# main.net
KiCad netlist of a schematic drawn in EAGLE
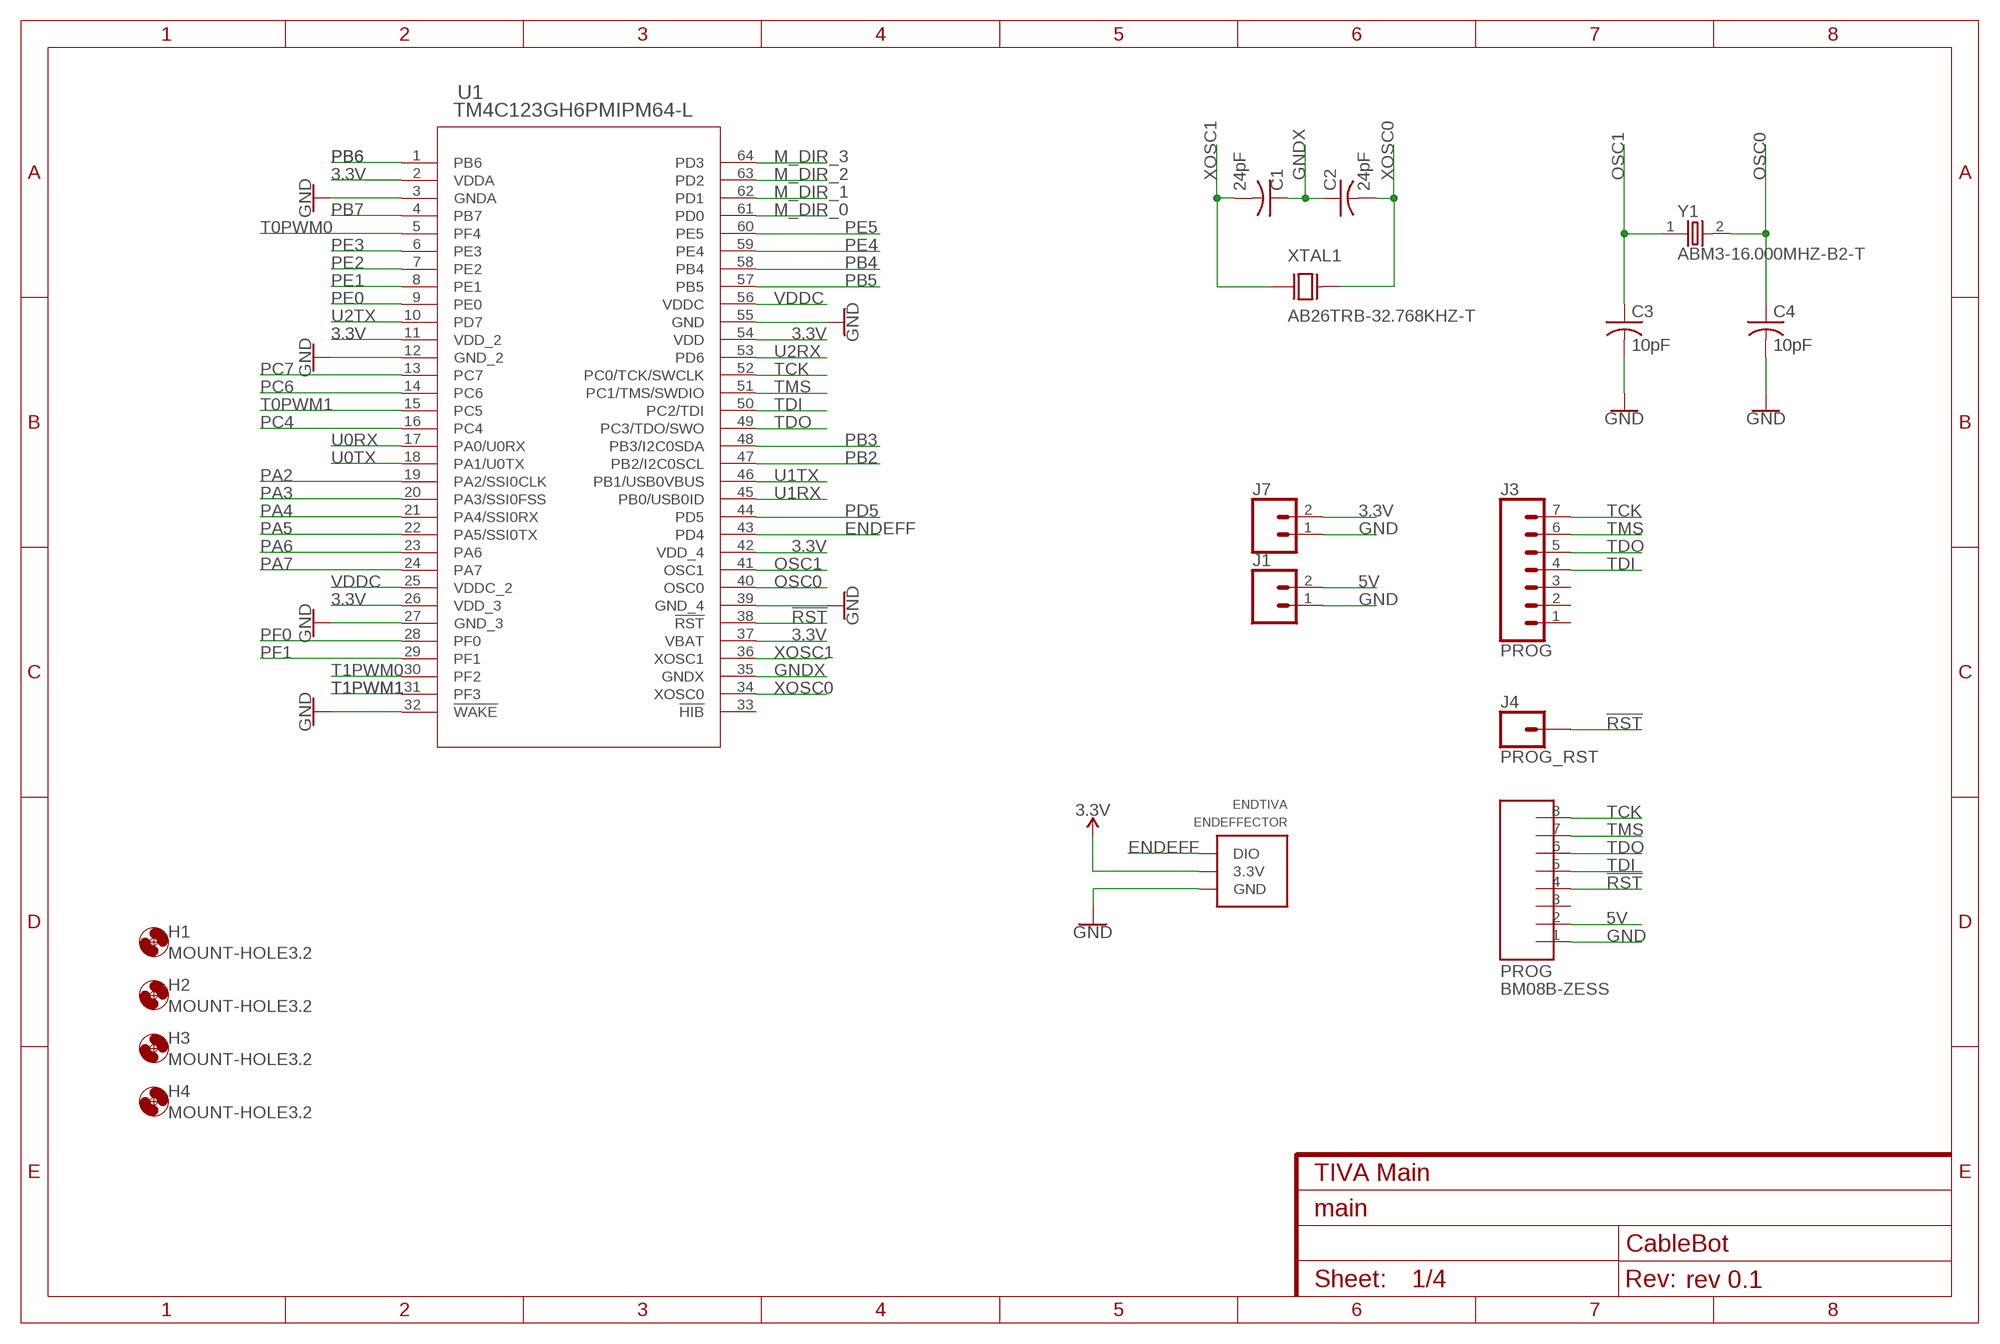
[diagram p0: schematic, sheet 1]
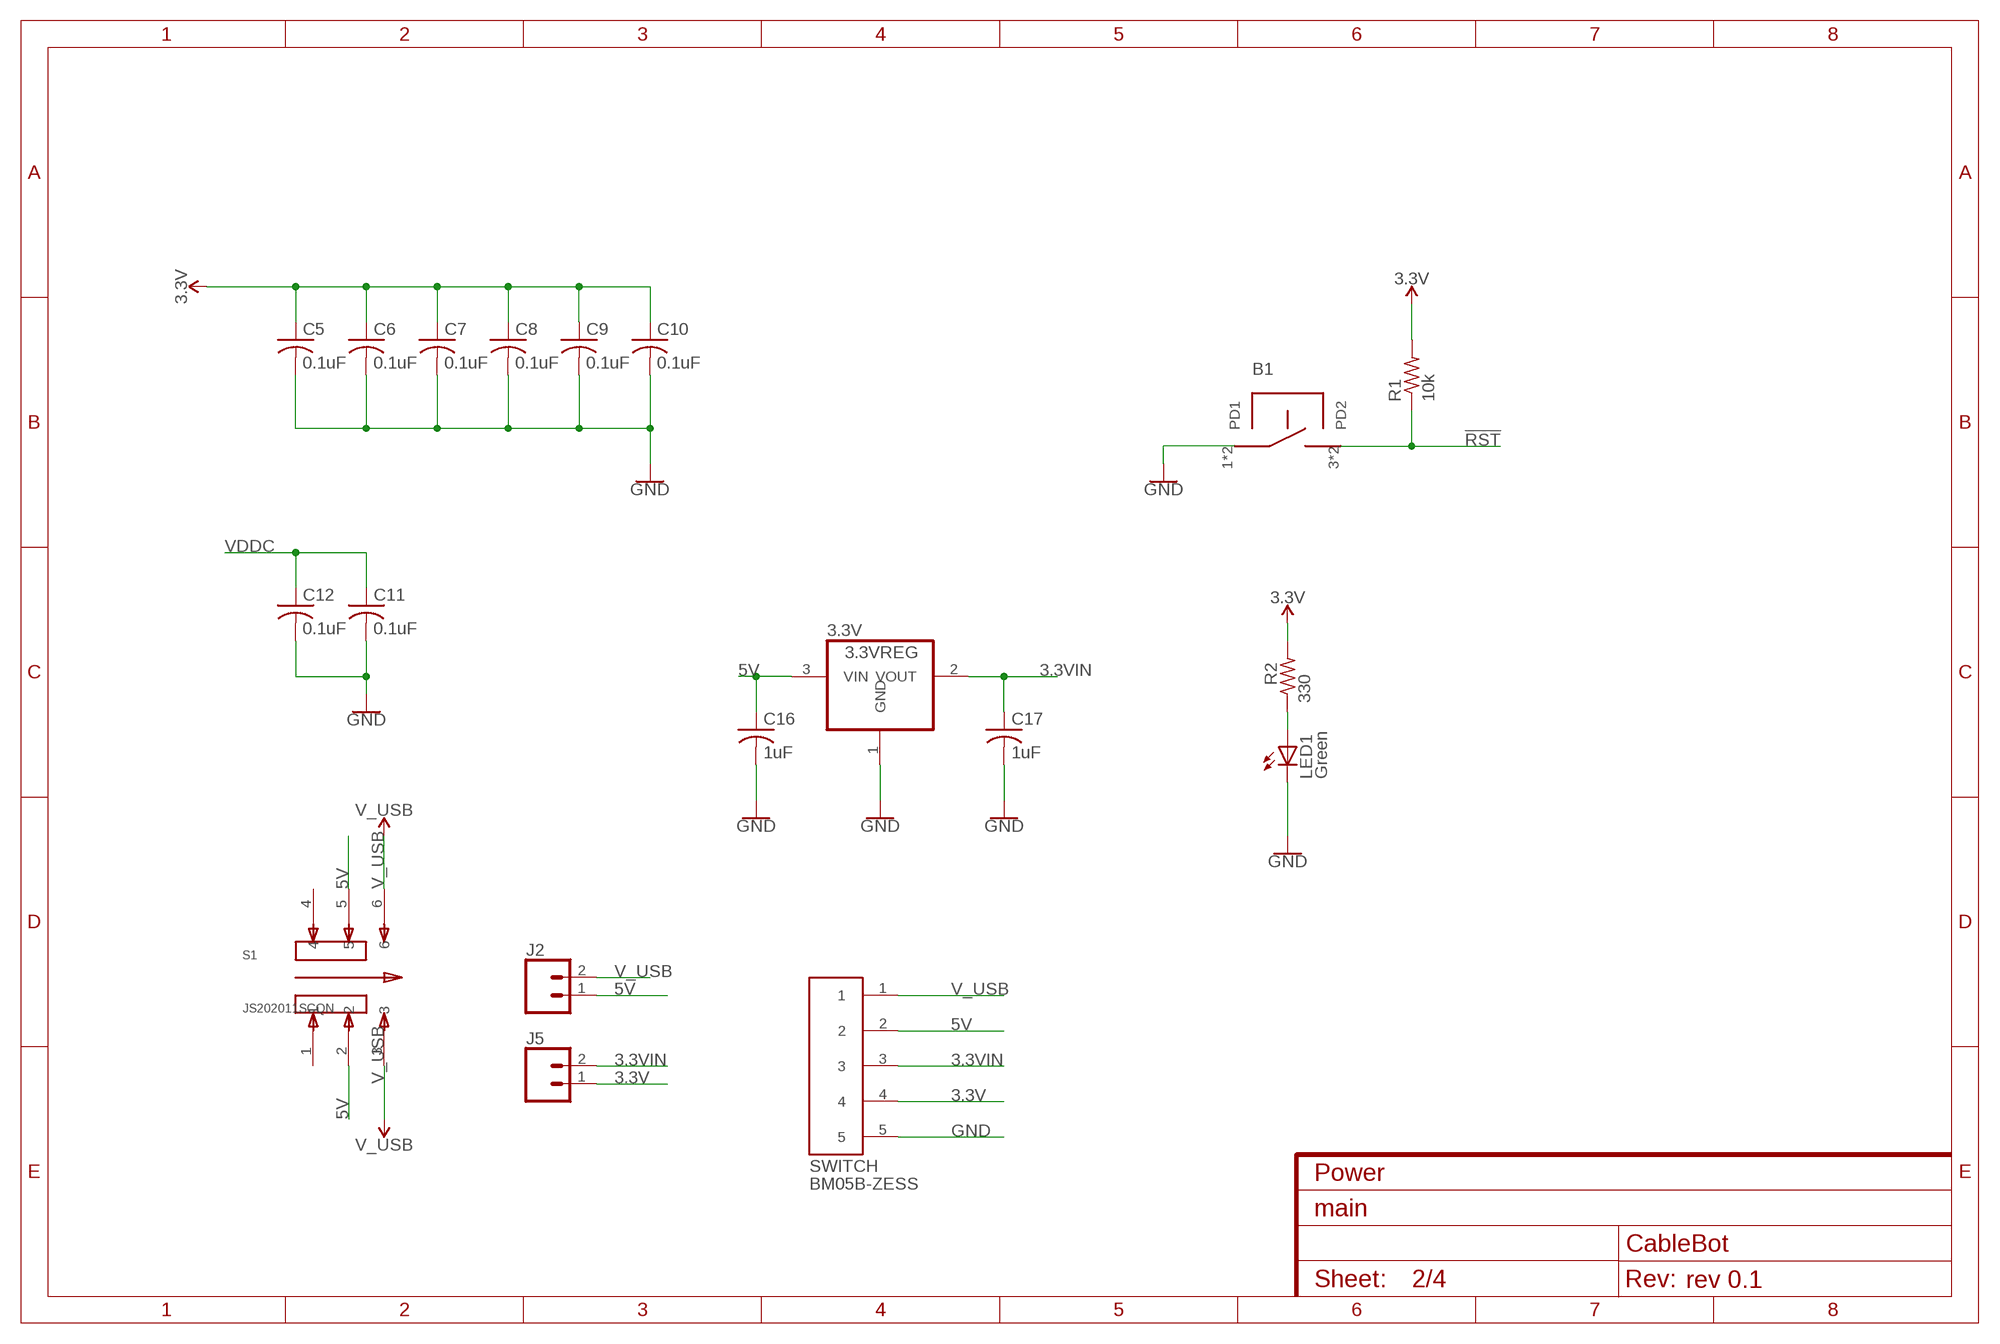
[diagram p1: schematic, sheet 2]
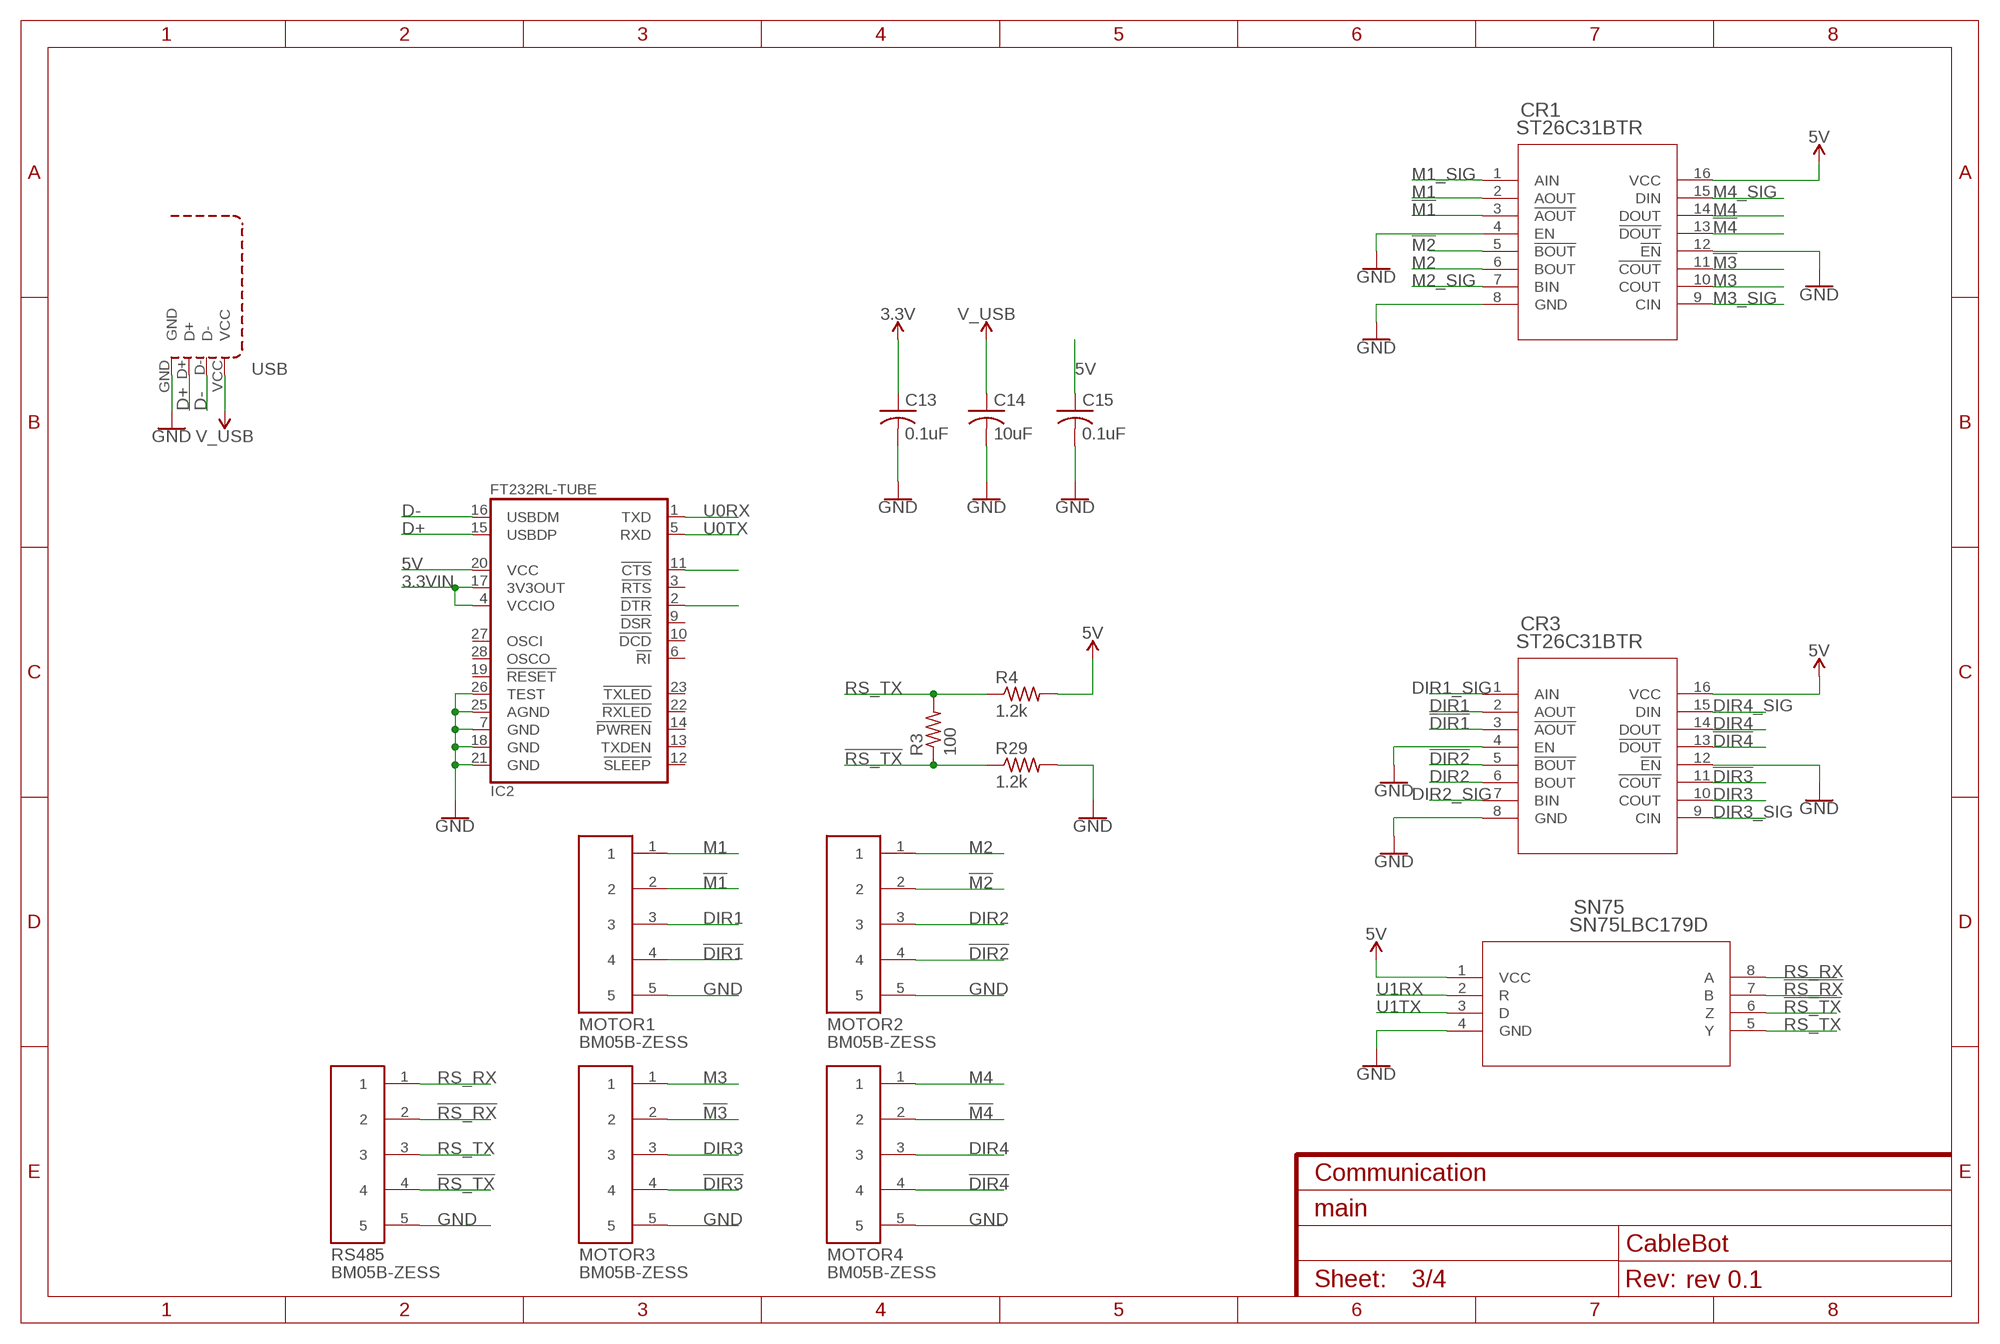
[diagram p2: schematic, sheet 3]
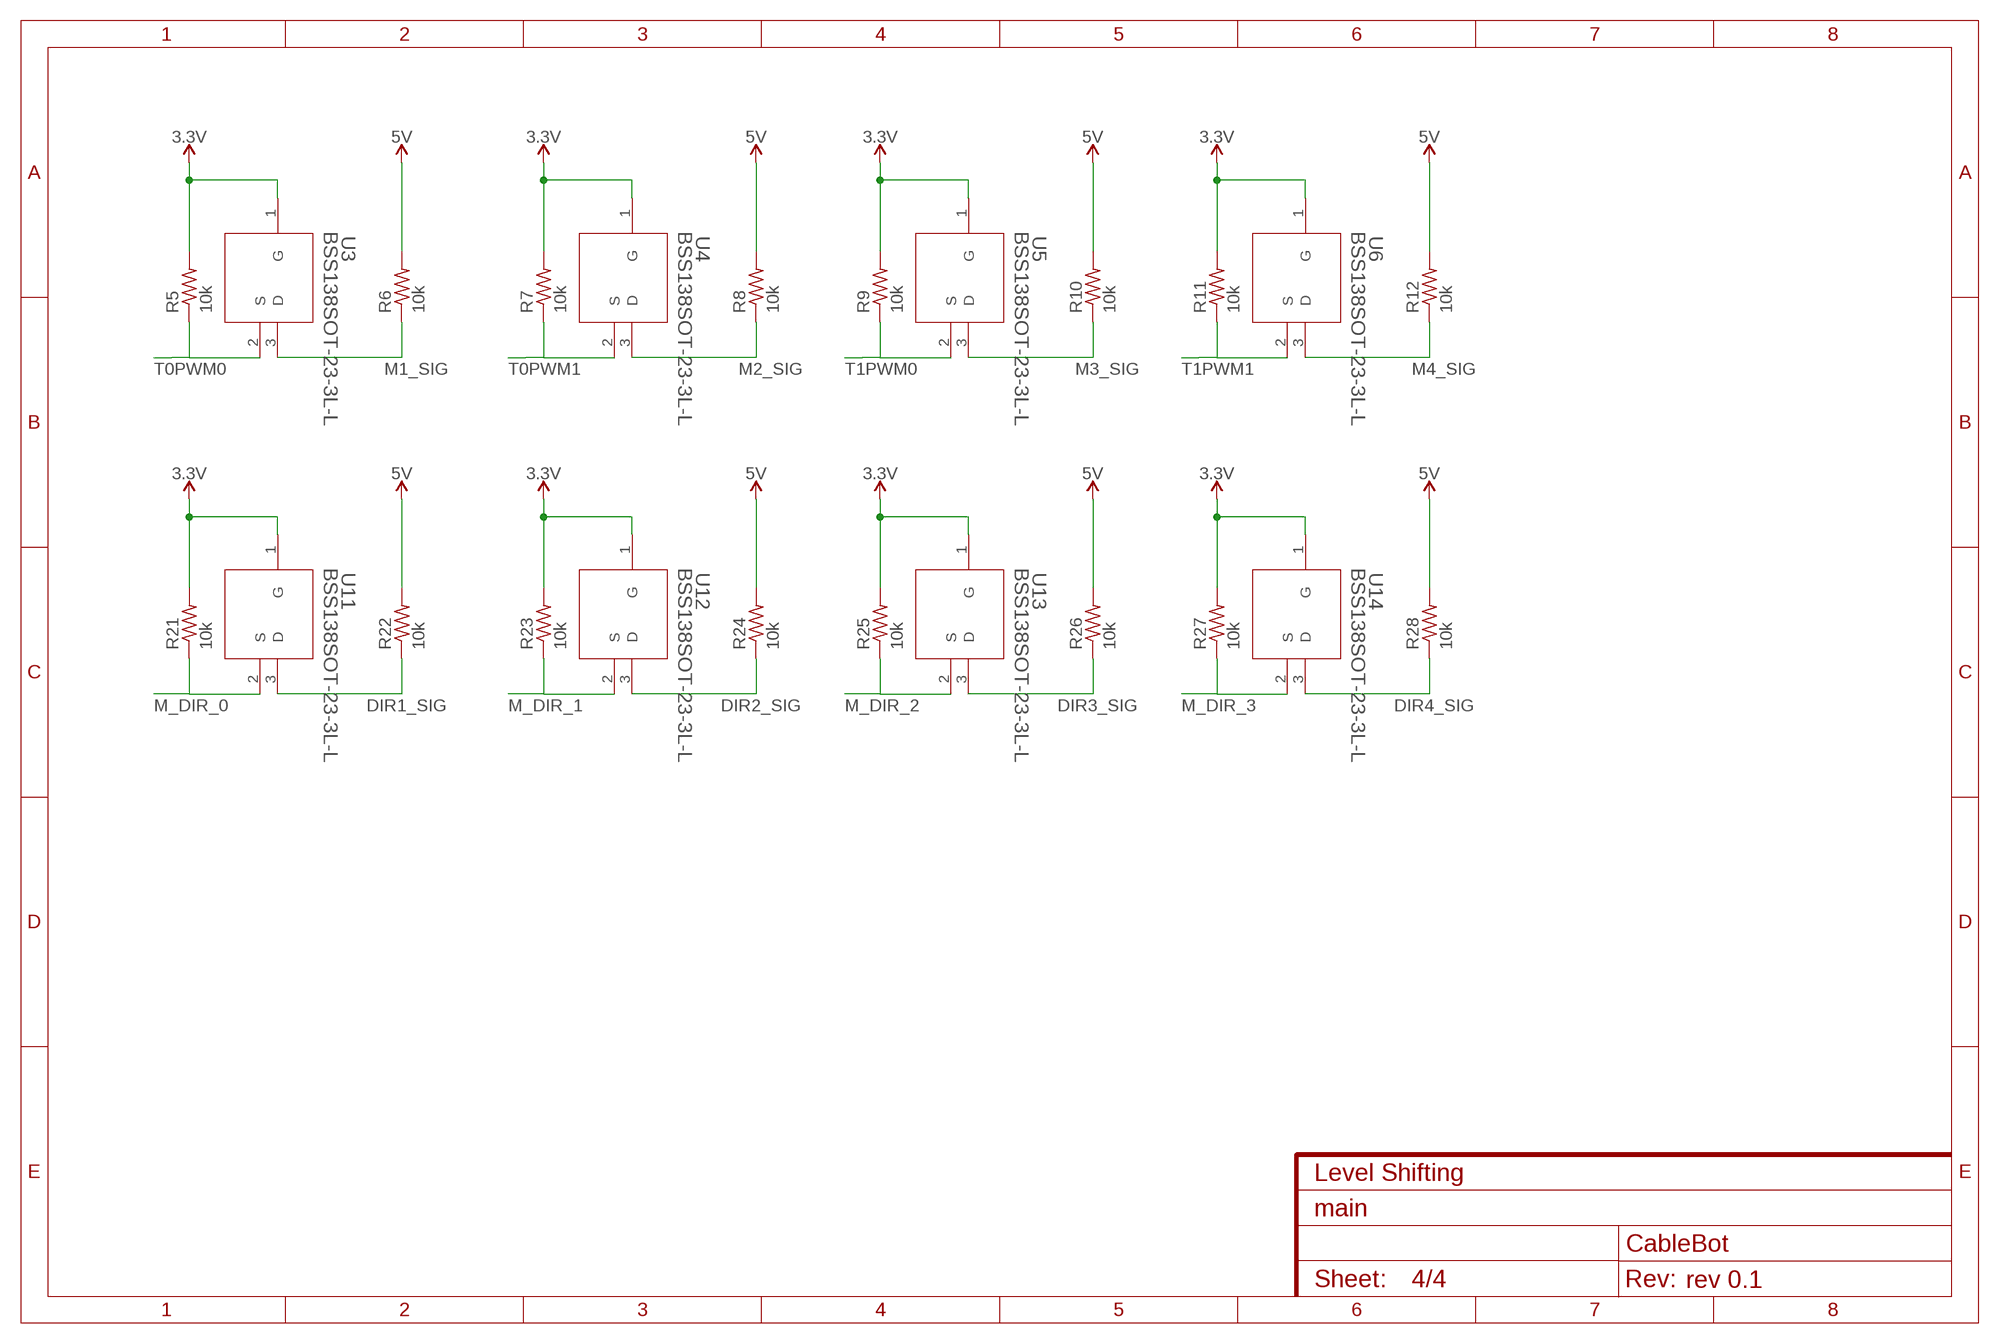
[diagram p3: schematic, sheet 4]

(export (version "E")
  (design (tool "Eeschema 10.0.6"))
  (components
    (comp (ref "C1")
      (value "24pF")
      (footprint "eagle-import:C0805")
      (libsource (lib "eagle-import") (part "C-USC0805"))
    )
    (comp (ref "C2")
      (value "24pF")
      (footprint "eagle-import:C0805")
      (libsource (lib "eagle-import") (part "C-USC0805"))
    )
    (comp (ref "C3")
      (value "10pF")
      (footprint "eagle-import:C0805")
      (libsource (lib "eagle-import") (part "C-USC0805"))
    )
    (comp (ref "C4")
      (value "10pF")
      (footprint "eagle-import:C0805")
      (libsource (lib "eagle-import") (part "C-USC0805"))
    )
    (comp (ref "ENDEFFECTOR")
      (value "ENDTIVA")
      (footprint "eagle-import:ENDTIVA")
      (libsource (lib "eagle-import") (part "ENDTIVA"))
    )
    (comp (ref "H1")
      (value "MOUNT-HOLE3.2")
      (footprint "eagle-import:3,2")
      (libsource (lib "eagle-import") (part "MOUNT-HOLE3.2"))
    )
    (comp (ref "H2")
      (value "MOUNT-HOLE3.2")
      (footprint "eagle-import:3,2")
      (libsource (lib "eagle-import") (part "MOUNT-HOLE3.2"))
    )
    (comp (ref "H3")
      (value "MOUNT-HOLE3.2")
      (footprint "eagle-import:3,2")
      (libsource (lib "eagle-import") (part "MOUNT-HOLE3.2"))
    )
    (comp (ref "H4")
      (value "MOUNT-HOLE3.2")
      (footprint "eagle-import:3,2")
      (libsource (lib "eagle-import") (part "MOUNT-HOLE3.2"))
    )
    (comp (ref "J1")
      (value "CONN_02")
      (footprint "eagle-import:1X02")
      (libsource (lib "eagle-import") (part "CONN_02"))
    )
    (comp (ref "J3")
      (value "PROG")
      (footprint "eagle-import:1X07")
      (libsource (lib "eagle-import") (part "CONN_07"))
    )
    (comp (ref "J4")
      (value "PROG_RST")
      (footprint "eagle-import:1X01")
      (libsource (lib "eagle-import") (part "CONN_01"))
    )
    (comp (ref "J7")
      (value "CONN_02")
      (footprint "eagle-import:1X02")
      (libsource (lib "eagle-import") (part "CONN_02"))
    )
    (comp (ref "PROG")
      (value "BM08B-ZESS")
      (footprint "eagle-import:BM08B-ZESS")
      (libsource (lib "eagle-import") (part "BM08B-ZESS"))
    )
    (comp (ref "U1")
      (value "TM4C123GH6PMIPM64-L")
      (footprint "eagle-import:PM64-L")
      (fields (field (name "MANUFACTURER_PART_NUMBER") "TM4C123GH6PMI"))
      (libsource (lib "eagle-import") (part "TM4C123GH6PMIPM64-L"))
    )
    (comp (ref "XTAL1")
      (value "AB26TRB-32.768KHZ-T")
      (footprint "eagle-import:XTAL_AB26TRB-32.768KHZ-T")
      (fields (field (name "DIGI-KEY_PART_NUMBER") "535-9033-1-ND") (field (name "MF") "Abracon"))
      (libsource (lib "eagle-import") (part "AB26TRB-32.768KHZ-T"))
    )
    (comp (ref "Y1")
      (value "ABM3-16.000MHZ-B2-T")
      (footprint "eagle-import:XTAL500X320X130N")
      (fields (field (name "DIGI-KEY_PART_NUMBER") "535-9103-1-ND") (field (name "MF") "Abracon"))
      (libsource (lib "eagle-import") (part "ABM3-16.000MHZ-B2-T"))
    )
    (comp (ref "R5")
      (value "10k")
      (footprint "eagle-import:R0603")
      (libsource (lib "eagle-import") (part "R-US_R0603"))
    )
    (comp (ref "R6")
      (value "10k")
      (footprint "eagle-import:R0603")
      (libsource (lib "eagle-import") (part "R-US_R0603"))
    )
    (comp (ref "R7")
      (value "10k")
      (footprint "eagle-import:R0603")
      (libsource (lib "eagle-import") (part "R-US_R0603"))
    )
    (comp (ref "R8")
      (value "10k")
      (footprint "eagle-import:R0603")
      (libsource (lib "eagle-import") (part "R-US_R0603"))
    )
    (comp (ref "R9")
      (value "10k")
      (footprint "eagle-import:R0603")
      (libsource (lib "eagle-import") (part "R-US_R0603"))
    )
    (comp (ref "R10")
      (value "10k")
      (footprint "eagle-import:R0603")
      (libsource (lib "eagle-import") (part "R-US_R0603"))
    )
    (comp (ref "R11")
      (value "10k")
      (footprint "eagle-import:R0603")
      (libsource (lib "eagle-import") (part "R-US_R0603"))
    )
    (comp (ref "R12")
      (value "10k")
      (footprint "eagle-import:R0603")
      (libsource (lib "eagle-import") (part "R-US_R0603"))
    )
    (comp (ref "R21")
      (value "10k")
      (footprint "eagle-import:R0603")
      (libsource (lib "eagle-import") (part "R-US_R0603"))
    )
    (comp (ref "R22")
      (value "10k")
      (footprint "eagle-import:R0603")
      (libsource (lib "eagle-import") (part "R-US_R0603"))
    )
    (comp (ref "R23")
      (value "10k")
      (footprint "eagle-import:R0603")
      (libsource (lib "eagle-import") (part "R-US_R0603"))
    )
    (comp (ref "R24")
      (value "10k")
      (footprint "eagle-import:R0603")
      (libsource (lib "eagle-import") (part "R-US_R0603"))
    )
    (comp (ref "R25")
      (value "10k")
      (footprint "eagle-import:R0603")
      (libsource (lib "eagle-import") (part "R-US_R0603"))
    )
    (comp (ref "R26")
      (value "10k")
      (footprint "eagle-import:R0603")
      (libsource (lib "eagle-import") (part "R-US_R0603"))
    )
    (comp (ref "R27")
      (value "10k")
      (footprint "eagle-import:R0603")
      (libsource (lib "eagle-import") (part "R-US_R0603"))
    )
    (comp (ref "R28")
      (value "10k")
      (footprint "eagle-import:R0603")
      (libsource (lib "eagle-import") (part "R-US_R0603"))
    )
    (comp (ref "U3")
      (value "BSS138SOT-23-3L-L")
      (footprint "eagle-import:SOT-23-3L-L")
      (fields (field (name "MANUFACTURER_PART_NUMBER") "BSS138"))
      (libsource (lib "eagle-import") (part "BSS138SOT-23-3L-L"))
    )
    (comp (ref "U4")
      (value "BSS138SOT-23-3L-L")
      (footprint "eagle-import:SOT-23-3L-L")
      (fields (field (name "MANUFACTURER_PART_NUMBER") "BSS138"))
      (libsource (lib "eagle-import") (part "BSS138SOT-23-3L-L"))
    )
    (comp (ref "U5")
      (value "BSS138SOT-23-3L-L")
      (footprint "eagle-import:SOT-23-3L-L")
      (fields (field (name "MANUFACTURER_PART_NUMBER") "BSS138"))
      (libsource (lib "eagle-import") (part "BSS138SOT-23-3L-L"))
    )
    (comp (ref "U6")
      (value "BSS138SOT-23-3L-L")
      (footprint "eagle-import:SOT-23-3L-L")
      (fields (field (name "MANUFACTURER_PART_NUMBER") "BSS138"))
      (libsource (lib "eagle-import") (part "BSS138SOT-23-3L-L"))
    )
    (comp (ref "U11")
      (value "BSS138SOT-23-3L-L")
      (footprint "eagle-import:SOT-23-3L-L")
      (fields (field (name "MANUFACTURER_PART_NUMBER") "BSS138"))
      (libsource (lib "eagle-import") (part "BSS138SOT-23-3L-L"))
    )
    (comp (ref "U12")
      (value "BSS138SOT-23-3L-L")
      (footprint "eagle-import:SOT-23-3L-L")
      (fields (field (name "MANUFACTURER_PART_NUMBER") "BSS138"))
      (libsource (lib "eagle-import") (part "BSS138SOT-23-3L-L"))
    )
    (comp (ref "U13")
      (value "BSS138SOT-23-3L-L")
      (footprint "eagle-import:SOT-23-3L-L")
      (fields (field (name "MANUFACTURER_PART_NUMBER") "BSS138"))
      (libsource (lib "eagle-import") (part "BSS138SOT-23-3L-L"))
    )
    (comp (ref "U14")
      (value "BSS138SOT-23-3L-L")
      (footprint "eagle-import:SOT-23-3L-L")
      (fields (field (name "MANUFACTURER_PART_NUMBER") "BSS138"))
      (libsource (lib "eagle-import") (part "BSS138SOT-23-3L-L"))
    )
    (comp (ref "3.3V")
      (value "3.3VREG")
      (footprint "eagle-import:SOT223")
      (fields (field (name "MPN") "REG1117"))
      (libsource (lib "eagle-import") (part "REG1117"))
    )
    (comp (ref "B1")
      (value "B3S-1000")
      (footprint "eagle-import:SWITCH")
      (libsource (lib "eagle-import") (part "B3S-1000"))
    )
    (comp (ref "C5")
      (value "0.1uF")
      (footprint "eagle-import:C0805")
      (libsource (lib "eagle-import") (part "C-USC0805"))
    )
    (comp (ref "C6")
      (value "0.1uF")
      (footprint "eagle-import:C0805")
      (libsource (lib "eagle-import") (part "C-USC0805"))
    )
    (comp (ref "C7")
      (value "0.1uF")
      (footprint "eagle-import:C0805")
      (libsource (lib "eagle-import") (part "C-USC0805"))
    )
    (comp (ref "C8")
      (value "0.1uF")
      (footprint "eagle-import:C0805")
      (libsource (lib "eagle-import") (part "C-USC0805"))
    )
    (comp (ref "C9")
      (value "0.1uF")
      (footprint "eagle-import:C0805")
      (libsource (lib "eagle-import") (part "C-USC0805"))
    )
    (comp (ref "C10")
      (value "0.1uF")
      (footprint "eagle-import:C0805")
      (libsource (lib "eagle-import") (part "C-USC0805"))
    )
    (comp (ref "C11")
      (value "0.1uF")
      (footprint "eagle-import:C0805")
      (libsource (lib "eagle-import") (part "C-USC0805"))
    )
    (comp (ref "C12")
      (value "0.1uF")
      (footprint "eagle-import:C0805")
      (libsource (lib "eagle-import") (part "C-USC0805"))
    )
    (comp (ref "C16")
      (value "1uF")
      (footprint "eagle-import:C0805")
      (libsource (lib "eagle-import") (part "C-USC0805"))
    )
    (comp (ref "C17")
      (value "1uF")
      (footprint "eagle-import:C0805")
      (libsource (lib "eagle-import") (part "C-USC0805"))
    )
    (comp (ref "J2")
      (value "CONN_02")
      (footprint "eagle-import:1X02")
      (libsource (lib "eagle-import") (part "CONN_02"))
    )
    (comp (ref "J5")
      (value "CONN_02")
      (footprint "eagle-import:1X02")
      (libsource (lib "eagle-import") (part "CONN_02"))
    )
    (comp (ref "LED1")
      (value "Green")
      (footprint "eagle-import:CHIP-LED0805")
      (libsource (lib "eagle-import") (part "LEDCHIP-LED0805"))
    )
    (comp (ref "R1")
      (value "10k")
      (footprint "eagle-import:R0603")
      (libsource (lib "eagle-import") (part "adafruit_420_R-US_R0603"))
    )
    (comp (ref "R2")
      (value "330")
      (footprint "eagle-import:R0805")
      (libsource (lib "eagle-import") (part "adafruit_420_R-US_R0805"))
    )
    (comp (ref "S1")
      (value "JS202011SCQN")
      (footprint "eagle-import:SW_JS202011SCQN")
      (fields (field (name "MF") "C&K"))
      (libsource (lib "eagle-import") (part "JS202011SCQN"))
    )
    (comp (ref "SWITCH")
      (value "BM05B-ZESS")
      (footprint "eagle-import:BM05B-ZESS")
      (libsource (lib "eagle-import") (part "BM05B-ZESS"))
    )
    (comp (ref "C13")
      (value "0.1uF")
      (footprint "eagle-import:C0805")
      (libsource (lib "eagle-import") (part "C-USC0805"))
    )
    (comp (ref "C14")
      (value "10uF")
      (footprint "eagle-import:C0805")
      (libsource (lib "eagle-import") (part "C-USC0805"))
    )
    (comp (ref "C15")
      (value "0.1uF")
      (footprint "eagle-import:C0805")
      (libsource (lib "eagle-import") (part "C-USC0805"))
    )
    (comp (ref "CR1")
      (value "ST26C31BTR")
      (footprint "eagle-import:TSSOP16")
      (libsource (lib "eagle-import") (part "ST26C31BTR"))
    )
    (comp (ref "CR3")
      (value "ST26C31BTR")
      (footprint "eagle-import:TSSOP16")
      (libsource (lib "eagle-import") (part "ST26C31BTR"))
    )
    (comp (ref "IC2")
      (value "FT232RL-TUBE")
      (footprint "eagle-import:SSOP28-LD")
      (fields (field (name "DIGI-KEY_PART_NUMBER") "768-1306-ND") (field (name "MF") "FTDI,"))
      (libsource (lib "eagle-import") (part "FT232RL-TUBE"))
    )
    (comp (ref "MOTOR1")
      (value "BM05B-ZESS")
      (footprint "eagle-import:BM05B-ZESS")
      (libsource (lib "eagle-import") (part "BM05B-ZESS"))
    )
    (comp (ref "MOTOR2")
      (value "BM05B-ZESS")
      (footprint "eagle-import:BM05B-ZESS")
      (libsource (lib "eagle-import") (part "BM05B-ZESS"))
    )
    (comp (ref "MOTOR3")
      (value "BM05B-ZESS")
      (footprint "eagle-import:BM05B-ZESS")
      (libsource (lib "eagle-import") (part "BM05B-ZESS"))
    )
    (comp (ref "MOTOR4")
      (value "BM05B-ZESS")
      (footprint "eagle-import:BM05B-ZESS")
      (libsource (lib "eagle-import") (part "BM05B-ZESS"))
    )
    (comp (ref "R3")
      (value "100")
      (footprint "eagle-import:R0805")
      (libsource (lib "eagle-import") (part "resistor_348_R-US_R0805"))
    )
    (comp (ref "R4")
      (value "1.2k")
      (footprint "eagle-import:R0805")
      (libsource (lib "eagle-import") (part "resistor_348_R-US_R0805"))
    )
    (comp (ref "R29")
      (value "1.2k")
      (footprint "eagle-import:R0805")
      (libsource (lib "eagle-import") (part "resistor_348_R-US_R0805"))
    )
    (comp (ref "RS485")
      (value "BM05B-ZESS")
      (footprint "eagle-import:BM05B-ZESS")
      (libsource (lib "eagle-import") (part "BM05B-ZESS"))
    )
    (comp (ref "SN75")
      (value "SN75LBC179D")
      (footprint "eagle-import:D8")
      (libsource (lib "eagle-import") (part "SN75LBC179D"))
    )
    (comp (ref "USB")
      (value "ZX62MICROUSB")
      (footprint "eagle-import:ZX62-AB-5PA(11)")
      (libsource (lib "eagle-import") (part "ZX62MICROUSB"))
    )
  )
  (nets
    (net (code "1") (name "3.3V") (class "Default")
      (node (ref "C10") (pin "1") (pinfunction "1_1") (pintype "passive"))
      (node (ref "C13") (pin "1") (pinfunction "1_1") (pintype "passive"))
      (node (ref "C5") (pin "1") (pinfunction "1_1") (pintype "passive"))
      (node (ref "C6") (pin "1") (pinfunction "1_1") (pintype "passive"))
      (node (ref "C7") (pin "1") (pinfunction "1_1") (pintype "passive"))
      (node (ref "C8") (pin "1") (pinfunction "1_1") (pintype "passive"))
      (node (ref "C9") (pin "1") (pinfunction "1_1") (pintype "passive"))
      (node (ref "ENDEFFECTOR") (pin "3.3V") (pinfunction "3.3V_3.3V") (pintype "bidirectional"))
      (node (ref "J5") (pin "1") (pinfunction "1_1") (pintype "passive"))
      (node (ref "J7") (pin "2") (pinfunction "2_2") (pintype "passive"))
      (node (ref "R1") (pin "2") (pinfunction "2_2") (pintype "passive"))
      (node (ref "R11") (pin "2") (pinfunction "2_2") (pintype "passive"))
      (node (ref "R2") (pin "2") (pinfunction "2_2") (pintype "passive"))
      (node (ref "R21") (pin "2") (pinfunction "2_2") (pintype "passive"))
      (node (ref "R23") (pin "2") (pinfunction "2_2") (pintype "passive"))
      (node (ref "R25") (pin "2") (pinfunction "2_2") (pintype "passive"))
      (node (ref "R27") (pin "2") (pinfunction "2_2") (pintype "passive"))
      (node (ref "R5") (pin "2") (pinfunction "2_2") (pintype "passive"))
      (node (ref "R7") (pin "2") (pinfunction "2_2") (pintype "passive"))
      (node (ref "R9") (pin "2") (pinfunction "2_2") (pintype "passive"))
      (node (ref "SWITCH") (pin "4") (pinfunction "4_4") (pintype "bidirectional"))
      (node (ref "U1") (pin "11") (pinfunction "VDD_2_11") (pintype "power_in"))
      (node (ref "U1") (pin "2") (pinfunction "VDDA_2") (pintype "power_in"))
      (node (ref "U1") (pin "26") (pinfunction "VDD_3_26") (pintype "power_in"))
      (node (ref "U1") (pin "37") (pinfunction "VBAT_37") (pintype "power_in"))
      (node (ref "U1") (pin "42") (pinfunction "VDD_4_42") (pintype "power_in"))
      (node (ref "U1") (pin "54") (pinfunction "VDD_54") (pintype "power_in"))
      (node (ref "U11") (pin "1") (pinfunction "G_1") (pintype "passive"))
      (node (ref "U12") (pin "1") (pinfunction "G_1") (pintype "passive"))
      (node (ref "U13") (pin "1") (pinfunction "G_1") (pintype "passive"))
      (node (ref "U14") (pin "1") (pinfunction "G_1") (pintype "passive"))
      (node (ref "U3") (pin "1") (pinfunction "G_1") (pintype "passive"))
      (node (ref "U4") (pin "1") (pinfunction "G_1") (pintype "passive"))
      (node (ref "U5") (pin "1") (pinfunction "G_1") (pintype "passive"))
      (node (ref "U6") (pin "1") (pinfunction "G_1") (pintype "passive"))
    )
    (net (code "2") (name "3.3VIN") (class "Default")
      (node (ref "3.3V") (pin "2") (pinfunction "VOUT_2") (pintype "output"))
      (node (ref "C17") (pin "1") (pinfunction "1_1") (pintype "passive"))
      (node (ref "IC2") (pin "17") (pinfunction "3V3OUT_17") (pintype "power_in"))
      (node (ref "IC2") (pin "4") (pinfunction "VCCIO_4") (pintype "power_in"))
      (node (ref "J5") (pin "2") (pinfunction "2_2") (pintype "passive"))
      (node (ref "SWITCH") (pin "3") (pinfunction "3_3") (pintype "bidirectional"))
    )
    (net (code "3") (name "5V") (class "Default")
      (node (ref "3.3V") (pin "3") (pinfunction "VIN_3") (pintype "input"))
      (node (ref "C15") (pin "1") (pinfunction "1_1") (pintype "passive"))
      (node (ref "C16") (pin "1") (pinfunction "1_1") (pintype "passive"))
      (node (ref "CR1") (pin "16") (pinfunction "VCC_16") (pintype "power_in"))
      (node (ref "CR3") (pin "16") (pinfunction "VCC_16") (pintype "power_in"))
      (node (ref "IC2") (pin "20") (pinfunction "VCC_20") (pintype "power_in"))
      (node (ref "J1") (pin "2") (pinfunction "2_2") (pintype "passive"))
      (node (ref "J2") (pin "1") (pinfunction "1_1") (pintype "passive"))
      (node (ref "PROG") (pin "2") (pinfunction "P$2_2") (pintype "bidirectional"))
      (node (ref "R10") (pin "2") (pinfunction "2_2") (pintype "passive"))
      (node (ref "R12") (pin "2") (pinfunction "2_2") (pintype "passive"))
      (node (ref "R22") (pin "2") (pinfunction "2_2") (pintype "passive"))
      (node (ref "R24") (pin "2") (pinfunction "2_2") (pintype "passive"))
      (node (ref "R26") (pin "2") (pinfunction "2_2") (pintype "passive"))
      (node (ref "R28") (pin "2") (pinfunction "2_2") (pintype "passive"))
      (node (ref "R4") (pin "2") (pinfunction "2_2") (pintype "passive"))
      (node (ref "R6") (pin "2") (pinfunction "2_2") (pintype "passive"))
      (node (ref "R8") (pin "2") (pinfunction "2_2") (pintype "passive"))
      (node (ref "S1") (pin "2") (pinfunction "2_2") (pintype "passive"))
      (node (ref "S1") (pin "5") (pinfunction "5_5") (pintype "passive"))
      (node (ref "SN75") (pin "1") (pinfunction "VCC_1") (pintype "power_in"))
      (node (ref "SWITCH") (pin "2") (pinfunction "2_2") (pintype "bidirectional"))
    )
    (net (code "4") (name "D+") (class "Default")
      (node (ref "IC2") (pin "15") (pinfunction "USBDP_15") (pintype "bidirectional"))
      (node (ref "USB") (pin "D+") (pinfunction "D+_D+") (pintype "passive"))
    )
    (net (code "5") (name "D-") (class "Default")
      (node (ref "IC2") (pin "16") (pinfunction "USBDM_16") (pintype "bidirectional"))
      (node (ref "USB") (pin "D-") (pinfunction "D-_D-") (pintype "passive"))
    )
    (net (code "6") (name "DIR1") (class "Default")
      (node (ref "CR3") (pin "2") (pinfunction "AOUT_2") (pintype "output"))
      (node (ref "MOTOR1") (pin "3") (pinfunction "3_3") (pintype "bidirectional"))
    )
    (net (code "7") (name "DIR1_SIG") (class "Default")
      (node (ref "CR3") (pin "1") (pinfunction "AIN_1") (pintype "input"))
      (node (ref "R22") (pin "1") (pinfunction "1_1") (pintype "passive"))
      (node (ref "U11") (pin "3") (pinfunction "D_3") (pintype "passive"))
    )
    (net (code "8") (name "DIR2") (class "Default")
      (node (ref "CR3") (pin "6") (pinfunction "BOUT_6") (pintype "output"))
      (node (ref "MOTOR2") (pin "3") (pinfunction "3_3") (pintype "bidirectional"))
    )
    (net (code "9") (name "DIR2_SIG") (class "Default")
      (node (ref "CR3") (pin "7") (pinfunction "BIN_7") (pintype "input"))
      (node (ref "R24") (pin "1") (pinfunction "1_1") (pintype "passive"))
      (node (ref "U12") (pin "3") (pinfunction "D_3") (pintype "passive"))
    )
    (net (code "10") (name "DIR3") (class "Default")
      (node (ref "CR3") (pin "10") (pinfunction "COUT_10") (pintype "output"))
      (node (ref "MOTOR3") (pin "3") (pinfunction "3_3") (pintype "bidirectional"))
    )
    (net (code "11") (name "DIR3_SIG") (class "Default")
      (node (ref "CR3") (pin "9") (pinfunction "CIN_9") (pintype "input"))
      (node (ref "R26") (pin "1") (pinfunction "1_1") (pintype "passive"))
      (node (ref "U13") (pin "3") (pinfunction "D_3") (pintype "passive"))
    )
    (net (code "12") (name "DIR4") (class "Default")
      (node (ref "CR3") (pin "14") (pinfunction "DOUT_14") (pintype "output"))
      (node (ref "MOTOR4") (pin "3") (pinfunction "3_3") (pintype "bidirectional"))
    )
    (net (code "13") (name "DIR4_SIG") (class "Default")
      (node (ref "CR3") (pin "15") (pinfunction "DIN_15") (pintype "input"))
      (node (ref "R28") (pin "1") (pinfunction "1_1") (pintype "passive"))
      (node (ref "U14") (pin "3") (pinfunction "D_3") (pintype "passive"))
    )
    (net (code "14") (name "ENDEFF") (class "Default")
      (node (ref "ENDEFFECTOR") (pin "DIO") (pinfunction "DIO_DIO") (pintype "bidirectional"))
      (node (ref "U1") (pin "43") (pinfunction "PD4_43") (pintype "bidirectional"))
    )
    (net (code "15") (name "GND") (class "Default")
      (node (ref "3.3V") (pin "1") (pinfunction "GND_1") (pintype "power_in"))
      (node (ref "B1") (pin "1") (pinfunction "PD1_1") (pintype "bidirectional"))
      (node (ref "B1") (pin "2") (pinfunction "PD1_2") (pintype "bidirectional"))
      (node (ref "C10") (pin "2") (pinfunction "2_2") (pintype "passive"))
      (node (ref "C11") (pin "2") (pinfunction "2_2") (pintype "passive"))
      (node (ref "C12") (pin "2") (pinfunction "2_2") (pintype "passive"))
      (node (ref "C13") (pin "2") (pinfunction "2_2") (pintype "passive"))
      (node (ref "C14") (pin "2") (pinfunction "2_2") (pintype "passive"))
      (node (ref "C15") (pin "2") (pinfunction "2_2") (pintype "passive"))
      (node (ref "C16") (pin "2") (pinfunction "2_2") (pintype "passive"))
      (node (ref "C17") (pin "2") (pinfunction "2_2") (pintype "passive"))
      (node (ref "C3") (pin "2") (pinfunction "2_2") (pintype "passive"))
      (node (ref "C4") (pin "2") (pinfunction "2_2") (pintype "passive"))
      (node (ref "C5") (pin "2") (pinfunction "2_2") (pintype "passive"))
      (node (ref "C6") (pin "2") (pinfunction "2_2") (pintype "passive"))
      (node (ref "C7") (pin "2") (pinfunction "2_2") (pintype "passive"))
      (node (ref "C8") (pin "2") (pinfunction "2_2") (pintype "passive"))
      (node (ref "C9") (pin "2") (pinfunction "2_2") (pintype "passive"))
      (node (ref "CR1") (pin "12") (pinfunction "~{EN}_12") (pintype "passive"))
      (node (ref "CR1") (pin "4") (pinfunction "EN_4") (pintype "passive"))
      (node (ref "CR1") (pin "8") (pinfunction "GND_8") (pintype "power_in"))
      (node (ref "CR3") (pin "12") (pinfunction "~{EN}_12") (pintype "passive"))
      (node (ref "CR3") (pin "4") (pinfunction "EN_4") (pintype "passive"))
      (node (ref "CR3") (pin "8") (pinfunction "GND_8") (pintype "power_in"))
      (node (ref "ENDEFFECTOR") (pin "GND") (pinfunction "GND_GND") (pintype "bidirectional"))
      (node (ref "IC2") (pin "18") (pinfunction "GND_18") (pintype "power_in"))
      (node (ref "IC2") (pin "21") (pinfunction "GND_21") (pintype "power_in"))
      (node (ref "IC2") (pin "25") (pinfunction "AGND_25") (pintype "power_in"))
      (node (ref "IC2") (pin "26") (pinfunction "TEST_26") (pintype "input"))
      (node (ref "IC2") (pin "7") (pinfunction "GND_7") (pintype "power_in"))
      (node (ref "J1") (pin "1") (pinfunction "1_1") (pintype "passive"))
      (node (ref "J7") (pin "1") (pinfunction "1_1") (pintype "passive"))
      (node (ref "LED1") (pin "C") (pinfunction "C_C") (pintype "passive"))
      (node (ref "MOTOR1") (pin "5") (pinfunction "5_5") (pintype "bidirectional"))
      (node (ref "MOTOR2") (pin "5") (pinfunction "5_5") (pintype "bidirectional"))
      (node (ref "MOTOR3") (pin "5") (pinfunction "5_5") (pintype "bidirectional"))
      (node (ref "MOTOR4") (pin "5") (pinfunction "5_5") (pintype "bidirectional"))
      (node (ref "PROG") (pin "1") (pinfunction "P$1_1") (pintype "bidirectional"))
      (node (ref "R29") (pin "2") (pinfunction "2_2") (pintype "passive"))
      (node (ref "RS485") (pin "5") (pinfunction "5_5") (pintype "bidirectional"))
      (node (ref "SN75") (pin "4") (pinfunction "GND_4") (pintype "power_in"))
      (node (ref "SWITCH") (pin "5") (pinfunction "5_5") (pintype "bidirectional"))
      (node (ref "U1") (pin "12") (pinfunction "GND_2_12") (pintype "power_in"))
      (node (ref "U1") (pin "27") (pinfunction "GND_3_27") (pintype "power_in"))
      (node (ref "U1") (pin "3") (pinfunction "GNDA_3") (pintype "power_in"))
      (node (ref "U1") (pin "32") (pinfunction "~{WAKE}_32") (pintype "input"))
      (node (ref "U1") (pin "39") (pinfunction "GND_4_39") (pintype "power_in"))
      (node (ref "U1") (pin "55") (pinfunction "GND_55") (pintype "power_in"))
      (node (ref "USB") (pin "GND") (pinfunction "GND_GND") (pintype "passive"))
    )
    (net (code "16") (name "GNDX") (class "Default")
      (node (ref "C1") (pin "1") (pinfunction "1_1") (pintype "passive"))
      (node (ref "C2") (pin "1") (pinfunction "1_1") (pintype "passive"))
      (node (ref "U1") (pin "35") (pinfunction "GNDX_35") (pintype "power_in"))
    )
    (net (code "17") (name "M1") (class "Default")
      (node (ref "CR1") (pin "2") (pinfunction "AOUT_2") (pintype "output"))
      (node (ref "MOTOR1") (pin "1") (pinfunction "1_1") (pintype "bidirectional"))
    )
    (net (code "18") (name "M1_SIG") (class "Default")
      (node (ref "CR1") (pin "1") (pinfunction "AIN_1") (pintype "input"))
      (node (ref "R6") (pin "1") (pinfunction "1_1") (pintype "passive"))
      (node (ref "U3") (pin "3") (pinfunction "D_3") (pintype "passive"))
    )
    (net (code "19") (name "M2") (class "Default")
      (node (ref "CR1") (pin "6") (pinfunction "BOUT_6") (pintype "output"))
      (node (ref "MOTOR2") (pin "1") (pinfunction "1_1") (pintype "bidirectional"))
    )
    (net (code "20") (name "M2_SIG") (class "Default")
      (node (ref "CR1") (pin "7") (pinfunction "BIN_7") (pintype "input"))
      (node (ref "R8") (pin "1") (pinfunction "1_1") (pintype "passive"))
      (node (ref "U4") (pin "3") (pinfunction "D_3") (pintype "passive"))
    )
    (net (code "21") (name "M3") (class "Default")
      (node (ref "CR1") (pin "10") (pinfunction "COUT_10") (pintype "output"))
      (node (ref "MOTOR3") (pin "1") (pinfunction "1_1") (pintype "bidirectional"))
    )
    (net (code "22") (name "M3_SIG") (class "Default")
      (node (ref "CR1") (pin "9") (pinfunction "CIN_9") (pintype "input"))
      (node (ref "R10") (pin "1") (pinfunction "1_1") (pintype "passive"))
      (node (ref "U5") (pin "3") (pinfunction "D_3") (pintype "passive"))
    )
    (net (code "23") (name "M4") (class "Default")
      (node (ref "CR1") (pin "14") (pinfunction "DOUT_14") (pintype "output"))
      (node (ref "MOTOR4") (pin "1") (pinfunction "1_1") (pintype "bidirectional"))
    )
    (net (code "24") (name "M4_SIG") (class "Default")
      (node (ref "CR1") (pin "15") (pinfunction "DIN_15") (pintype "input"))
      (node (ref "R12") (pin "1") (pinfunction "1_1") (pintype "passive"))
      (node (ref "U6") (pin "3") (pinfunction "D_3") (pintype "passive"))
    )
    (net (code "25") (name "M_DIR_0") (class "Default")
      (node (ref "R21") (pin "1") (pinfunction "1_1") (pintype "passive"))
      (node (ref "U1") (pin "61") (pinfunction "PD0_61") (pintype "bidirectional"))
      (node (ref "U11") (pin "2") (pinfunction "S_2") (pintype "passive"))
    )
    (net (code "26") (name "M_DIR_1") (class "Default")
      (node (ref "R23") (pin "1") (pinfunction "1_1") (pintype "passive"))
      (node (ref "U1") (pin "62") (pinfunction "PD1_62") (pintype "bidirectional"))
      (node (ref "U12") (pin "2") (pinfunction "S_2") (pintype "passive"))
    )
    (net (code "27") (name "M_DIR_2") (class "Default")
      (node (ref "R25") (pin "1") (pinfunction "1_1") (pintype "passive"))
      (node (ref "U1") (pin "63") (pinfunction "PD2_63") (pintype "bidirectional"))
      (node (ref "U13") (pin "2") (pinfunction "S_2") (pintype "passive"))
    )
    (net (code "28") (name "M_DIR_3") (class "Default")
      (node (ref "R27") (pin "1") (pinfunction "1_1") (pintype "passive"))
      (node (ref "U1") (pin "64") (pinfunction "PD3_64") (pintype "bidirectional"))
      (node (ref "U14") (pin "2") (pinfunction "S_2") (pintype "passive"))
    )
    (net (code "29") (name "Net-(LED1-PadA)") (class "Default")
      (node (ref "LED1") (pin "A") (pinfunction "A_A") (pintype "passive"))
      (node (ref "R2") (pin "1") (pinfunction "1_1") (pintype "passive"))
    )
    (net (code "30") (name "OSC0") (class "Default")
      (node (ref "C4") (pin "1") (pinfunction "1_1") (pintype "passive"))
      (node (ref "U1") (pin "40") (pinfunction "OSC0_40") (pintype "input"))
      (node (ref "Y1") (pin "2") (pinfunction "2_2") (pintype "passive"))
    )
    (net (code "31") (name "OSC1") (class "Default")
      (node (ref "C3") (pin "1") (pinfunction "1_1") (pintype "passive"))
      (node (ref "U1") (pin "41") (pinfunction "OSC1_41") (pintype "output"))
      (node (ref "Y1") (pin "1") (pinfunction "1_1") (pintype "passive"))
    )
    (net (code "32") (name "PA2") (class "Default")
      (node (ref "U1") (pin "19") (pinfunction "PA2/SSI0CLK_19") (pintype "bidirectional"))
    )
    (net (code "33") (name "PA3") (class "Default")
      (node (ref "U1") (pin "20") (pinfunction "PA3/SSI0FSS_20") (pintype "bidirectional"))
    )
    (net (code "34") (name "PA4") (class "Default")
      (node (ref "U1") (pin "21") (pinfunction "PA4/SSI0RX_21") (pintype "bidirectional"))
    )
    (net (code "35") (name "PA5") (class "Default")
      (node (ref "U1") (pin "22") (pinfunction "PA5/SSI0TX_22") (pintype "bidirectional"))
    )
    (net (code "36") (name "PA6") (class "Default")
      (node (ref "U1") (pin "23") (pinfunction "PA6_23") (pintype "bidirectional"))
    )
    (net (code "37") (name "PA7") (class "Default")
      (node (ref "U1") (pin "24") (pinfunction "PA7_24") (pintype "bidirectional"))
    )
    (net (code "38") (name "PB2") (class "Default")
      (node (ref "U1") (pin "47") (pinfunction "PB2/I2C0SCL_47") (pintype "bidirectional"))
    )
    (net (code "39") (name "PB3") (class "Default")
      (node (ref "U1") (pin "48") (pinfunction "PB3/I2C0SDA_48") (pintype "bidirectional"))
    )
    (net (code "40") (name "PB4") (class "Default")
      (node (ref "U1") (pin "58") (pinfunction "PB4_58") (pintype "bidirectional"))
    )
    (net (code "41") (name "PB5") (class "Default")
      (node (ref "U1") (pin "57") (pinfunction "PB5_57") (pintype "bidirectional"))
    )
    (net (code "42") (name "PB6") (class "Default")
      (node (ref "U1") (pin "1") (pinfunction "PB6_1") (pintype "bidirectional"))
    )
    (net (code "43") (name "PB7") (class "Default")
      (node (ref "U1") (pin "4") (pinfunction "PB7_4") (pintype "bidirectional"))
    )
    (net (code "44") (name "PC4") (class "Default")
      (node (ref "U1") (pin "16") (pinfunction "PC4_16") (pintype "bidirectional"))
    )
    (net (code "45") (name "PC6") (class "Default")
      (node (ref "U1") (pin "14") (pinfunction "PC6_14") (pintype "bidirectional"))
    )
    (net (code "46") (name "PC7") (class "Default")
      (node (ref "U1") (pin "13") (pinfunction "PC7_13") (pintype "bidirectional"))
    )
    (net (code "47") (name "PD5") (class "Default")
      (node (ref "U1") (pin "44") (pinfunction "PD5_44") (pintype "bidirectional"))
    )
    (net (code "48") (name "PE0") (class "Default")
      (node (ref "U1") (pin "9") (pinfunction "PE0_9") (pintype "bidirectional"))
    )
    (net (code "49") (name "PE1") (class "Default")
      (node (ref "U1") (pin "8") (pinfunction "PE1_8") (pintype "bidirectional"))
    )
    (net (code "50") (name "PE2") (class "Default")
      (node (ref "U1") (pin "7") (pinfunction "PE2_7") (pintype "bidirectional"))
    )
    (net (code "51") (name "PE3") (class "Default")
      (node (ref "U1") (pin "6") (pinfunction "PE3_6") (pintype "bidirectional"))
    )
    (net (code "52") (name "PE4") (class "Default")
      (node (ref "U1") (pin "59") (pinfunction "PE4_59") (pintype "bidirectional"))
    )
    (net (code "53") (name "PE5") (class "Default")
      (node (ref "U1") (pin "60") (pinfunction "PE5_60") (pintype "bidirectional"))
    )
    (net (code "54") (name "PF0") (class "Default")
      (node (ref "U1") (pin "28") (pinfunction "PF0_28") (pintype "bidirectional"))
    )
    (net (code "55") (name "PF1") (class "Default")
      (node (ref "U1") (pin "29") (pinfunction "PF1_29") (pintype "bidirectional"))
    )
    (net (code "56") (name "RS_RX") (class "Default")
      (node (ref "RS485") (pin "1") (pinfunction "1_1") (pintype "bidirectional"))
      (node (ref "SN75") (pin "8") (pinfunction "A_8") (pintype "output"))
    )
    (net (code "57") (name "RS_TX") (class "Default")
      (node (ref "R3") (pin "2") (pinfunction "2_2") (pintype "passive"))
      (node (ref "R4") (pin "1") (pinfunction "1_1") (pintype "passive"))
      (node (ref "RS485") (pin "3") (pinfunction "3_3") (pintype "bidirectional"))
      (node (ref "SN75") (pin "5") (pinfunction "Y_5") (pintype "output"))
    )
    (net (code "58") (name "T0PWM0") (class "Default")
      (node (ref "R5") (pin "1") (pinfunction "1_1") (pintype "passive"))
      (node (ref "U1") (pin "5") (pinfunction "PF4_5") (pintype "bidirectional"))
      (node (ref "U3") (pin "2") (pinfunction "S_2") (pintype "passive"))
    )
    (net (code "59") (name "T0PWM1") (class "Default")
      (node (ref "R7") (pin "1") (pinfunction "1_1") (pintype "passive"))
      (node (ref "U1") (pin "15") (pinfunction "PC5_15") (pintype "bidirectional"))
      (node (ref "U4") (pin "2") (pinfunction "S_2") (pintype "passive"))
    )
    (net (code "60") (name "T1PWM0") (class "Default")
      (node (ref "R9") (pin "1") (pinfunction "1_1") (pintype "passive"))
      (node (ref "U1") (pin "30") (pinfunction "PF2_30") (pintype "bidirectional"))
      (node (ref "U5") (pin "2") (pinfunction "S_2") (pintype "passive"))
    )
    (net (code "61") (name "T1PWM1") (class "Default")
      (node (ref "R11") (pin "1") (pinfunction "1_1") (pintype "passive"))
      (node (ref "U1") (pin "31") (pinfunction "PF3_31") (pintype "bidirectional"))
      (node (ref "U6") (pin "2") (pinfunction "S_2") (pintype "passive"))
    )
    (net (code "62") (name "TCK") (class "Default")
      (node (ref "J3") (pin "7") (pinfunction "7_7") (pintype "passive"))
      (node (ref "PROG") (pin "8") (pinfunction "P$8_8") (pintype "bidirectional"))
      (node (ref "U1") (pin "52") (pinfunction "PC0/TCK/SWCLK_52") (pintype "bidirectional"))
    )
    (net (code "63") (name "TDI") (class "Default")
      (node (ref "J3") (pin "4") (pinfunction "4_4") (pintype "passive"))
      (node (ref "PROG") (pin "5") (pinfunction "P$5_5") (pintype "bidirectional"))
      (node (ref "U1") (pin "50") (pinfunction "PC2/TDI_50") (pintype "bidirectional"))
    )
    (net (code "64") (name "TDO") (class "Default")
      (node (ref "J3") (pin "5") (pinfunction "5_5") (pintype "passive"))
      (node (ref "PROG") (pin "6") (pinfunction "P$6_6") (pintype "bidirectional"))
      (node (ref "U1") (pin "49") (pinfunction "PC3/TDO/SWO_49") (pintype "bidirectional"))
    )
    (net (code "65") (name "TMS") (class "Default")
      (node (ref "J3") (pin "6") (pinfunction "6_6") (pintype "passive"))
      (node (ref "PROG") (pin "7") (pinfunction "P$7_7") (pintype "bidirectional"))
      (node (ref "U1") (pin "51") (pinfunction "PC1/TMS/SWDIO_51") (pintype "bidirectional"))
    )
    (net (code "66") (name "U0RX") (class "Default")
      (node (ref "IC2") (pin "1") (pinfunction "TXD_1") (pintype "output"))
      (node (ref "U1") (pin "17") (pinfunction "PA0/U0RX_17") (pintype "bidirectional"))
    )
    (net (code "67") (name "U0TX") (class "Default")
      (node (ref "IC2") (pin "5") (pinfunction "RXD_5") (pintype "input"))
      (node (ref "U1") (pin "18") (pinfunction "PA1/U0TX_18") (pintype "bidirectional"))
    )
    (net (code "68") (name "U1RX") (class "Default")
      (node (ref "SN75") (pin "2") (pinfunction "R_2") (pintype "input"))
      (node (ref "U1") (pin "45") (pinfunction "PB0/USB0ID_45") (pintype "bidirectional"))
    )
    (net (code "69") (name "U1TX") (class "Default")
      (node (ref "SN75") (pin "3") (pinfunction "D_3") (pintype "input"))
      (node (ref "U1") (pin "46") (pinfunction "PB1/USB0VBUS_46") (pintype "bidirectional"))
    )
    (net (code "70") (name "U2RX") (class "Default")
      (node (ref "U1") (pin "53") (pinfunction "PD6_53") (pintype "bidirectional"))
    )
    (net (code "71") (name "U2TX") (class "Default")
      (node (ref "U1") (pin "10") (pinfunction "PD7_10") (pintype "bidirectional"))
    )
    (net (code "72") (name "VDDC") (class "Default")
      (node (ref "C11") (pin "1") (pinfunction "1_1") (pintype "passive"))
      (node (ref "C12") (pin "1") (pinfunction "1_1") (pintype "passive"))
      (node (ref "U1") (pin "25") (pinfunction "VDDC_2_25") (pintype "power_in"))
      (node (ref "U1") (pin "56") (pinfunction "VDDC_56") (pintype "power_in"))
    )
    (net (code "73") (name "V_USB") (class "Default")
      (node (ref "C14") (pin "1") (pinfunction "1_1") (pintype "passive"))
      (node (ref "J2") (pin "2") (pinfunction "2_2") (pintype "passive"))
      (node (ref "S1") (pin "3") (pinfunction "3_3") (pintype "passive"))
      (node (ref "S1") (pin "6") (pinfunction "6_6") (pintype "passive"))
      (node (ref "SWITCH") (pin "1") (pinfunction "1_1") (pintype "bidirectional"))
      (node (ref "USB") (pin "VCC") (pinfunction "VCC_VCC") (pintype "passive"))
    )
    (net (code "74") (name "XOSC0") (class "Default")
      (node (ref "C2") (pin "2") (pinfunction "2_2") (pintype "passive"))
      (node (ref "U1") (pin "34") (pinfunction "XOSC0_34") (pintype "input"))
      (node (ref "XTAL1") (pin "2") (pinfunction "2_2") (pintype "passive"))
    )
    (net (code "75") (name "XOSC1") (class "Default")
      (node (ref "C1") (pin "2") (pinfunction "2_2") (pintype "passive"))
      (node (ref "U1") (pin "36") (pinfunction "XOSC1_36") (pintype "output"))
      (node (ref "XTAL1") (pin "1") (pinfunction "1_1") (pintype "passive"))
    )
    (net (code "76") (name "unconnected-(IC2-OSCI-Pad27)") (class "Default")
      (node (ref "IC2") (pin "27") (pinfunction "OSCI_27") (pintype "no_connect"))
    )
    (net (code "77") (name "unconnected-(IC2-OSCO-Pad28)") (class "Default")
      (node (ref "IC2") (pin "28") (pinfunction "OSCO_28") (pintype "output"))
    )
    (net (code "78") (name "unconnected-(IC2-TXDEN-Pad13)") (class "Default")
      (node (ref "IC2") (pin "13") (pinfunction "TXDEN_13") (pintype "no_connect"))
    )
    (net (code "79") (name "unconnected-(IC2-~{CTS}-Pad11)") (class "Default")
      (node (ref "IC2") (pin "11") (pinfunction "~{CTS}_11") (pintype "input"))
    )
    (net (code "80") (name "unconnected-(IC2-~{DCD}-Pad10)") (class "Default")
      (node (ref "IC2") (pin "10") (pinfunction "~{DCD}_10") (pintype "no_connect"))
    )
    (net (code "81") (name "unconnected-(IC2-~{DSR}-Pad9)") (class "Default")
      (node (ref "IC2") (pin "9") (pinfunction "~{DSR}_9") (pintype "no_connect"))
    )
    (net (code "82") (name "unconnected-(IC2-~{DTR}-Pad2)") (class "Default")
      (node (ref "IC2") (pin "2") (pinfunction "~{DTR}_2") (pintype "output"))
    )
    (net (code "83") (name "unconnected-(IC2-~{PWREN}-Pad14)") (class "Default")
      (node (ref "IC2") (pin "14") (pinfunction "~{PWREN}_14") (pintype "no_connect"))
    )
    (net (code "84") (name "unconnected-(IC2-~{RESET}-Pad19)") (class "Default")
      (node (ref "IC2") (pin "19") (pinfunction "~{RESET}_19") (pintype "no_connect"))
    )
    (net (code "85") (name "unconnected-(IC2-~{RI}-Pad6)") (class "Default")
      (node (ref "IC2") (pin "6") (pinfunction "~{RI}_6") (pintype "no_connect"))
    )
    (net (code "86") (name "unconnected-(IC2-~{RTS}-Pad3)") (class "Default")
      (node (ref "IC2") (pin "3") (pinfunction "~{RTS}_3") (pintype "output"))
    )
    (net (code "87") (name "unconnected-(IC2-~{RXLED}-Pad22)") (class "Default")
      (node (ref "IC2") (pin "22") (pinfunction "~{RXLED}_22") (pintype "input"))
    )
    (net (code "88") (name "unconnected-(IC2-~{SLEEP}-Pad12)") (class "Default")
      (node (ref "IC2") (pin "12") (pinfunction "~{SLEEP}_12") (pintype "no_connect"))
    )
    (net (code "89") (name "unconnected-(IC2-~{TXLED}-Pad23)") (class "Default")
      (node (ref "IC2") (pin "23") (pinfunction "~{TXLED}_23") (pintype "input"))
    )
    (net (code "90") (name "unconnected-(J3-Pad1)") (class "Default")
      (node (ref "J3") (pin "1") (pinfunction "1_1") (pintype "passive"))
    )
    (net (code "91") (name "unconnected-(J3-Pad2)") (class "Default")
      (node (ref "J3") (pin "2") (pinfunction "2_2") (pintype "passive"))
    )
    (net (code "92") (name "unconnected-(J3-Pad3)") (class "Default")
      (node (ref "J3") (pin "3") (pinfunction "3_3") (pintype "passive"))
    )
    (net (code "93") (name "unconnected-(PROG-P$3-Pad3)") (class "Default")
      (node (ref "PROG") (pin "3") (pinfunction "P$3_3") (pintype "bidirectional"))
    )
    (net (code "94") (name "unconnected-(S1-Pad1)") (class "Default")
      (node (ref "S1") (pin "1") (pinfunction "1_1") (pintype "passive"))
    )
    (net (code "95") (name "unconnected-(S1-Pad4)") (class "Default")
      (node (ref "S1") (pin "4") (pinfunction "4_4") (pintype "passive"))
    )
    (net (code "96") (name "unconnected-(U1-~{HIB}-Pad33)") (class "Default")
      (node (ref "U1") (pin "33") (pinfunction "~{HIB}_33") (pintype "output"))
    )
    (net (code "97") (name "~{DIR1}") (class "Default")
      (node (ref "CR3") (pin "3") (pinfunction "~{AOUT}_3") (pintype "output"))
      (node (ref "MOTOR1") (pin "4") (pinfunction "4_4") (pintype "bidirectional"))
    )
    (net (code "98") (name "~{DIR2}") (class "Default")
      (node (ref "CR3") (pin "5") (pinfunction "~{BOUT}_5") (pintype "output"))
      (node (ref "MOTOR2") (pin "4") (pinfunction "4_4") (pintype "bidirectional"))
    )
    (net (code "99") (name "~{DIR3}") (class "Default")
      (node (ref "CR3") (pin "11") (pinfunction "~{COUT}_11") (pintype "output"))
      (node (ref "MOTOR3") (pin "4") (pinfunction "4_4") (pintype "bidirectional"))
    )
    (net (code "100") (name "~{DIR4}") (class "Default")
      (node (ref "CR3") (pin "13") (pinfunction "~{DOUT}_13") (pintype "output"))
      (node (ref "MOTOR4") (pin "4") (pinfunction "4_4") (pintype "bidirectional"))
    )
    (net (code "101") (name "~{M1}") (class "Default")
      (node (ref "CR1") (pin "3") (pinfunction "~{AOUT}_3") (pintype "output"))
      (node (ref "MOTOR1") (pin "2") (pinfunction "2_2") (pintype "bidirectional"))
    )
    (net (code "102") (name "~{M2}") (class "Default")
      (node (ref "CR1") (pin "5") (pinfunction "~{BOUT}_5") (pintype "output"))
      (node (ref "MOTOR2") (pin "2") (pinfunction "2_2") (pintype "bidirectional"))
    )
    (net (code "103") (name "~{M3}") (class "Default")
      (node (ref "CR1") (pin "11") (pinfunction "~{COUT}_11") (pintype "output"))
      (node (ref "MOTOR3") (pin "2") (pinfunction "2_2") (pintype "bidirectional"))
    )
    (net (code "104") (name "~{M4}") (class "Default")
      (node (ref "CR1") (pin "13") (pinfunction "~{DOUT}_13") (pintype "output"))
      (node (ref "MOTOR4") (pin "2") (pinfunction "2_2") (pintype "bidirectional"))
    )
    (net (code "105") (name "~{RST}") (class "Default")
      (node (ref "B1") (pin "3") (pinfunction "PD2_3") (pintype "bidirectional"))
      (node (ref "B1") (pin "4") (pinfunction "PD2_4") (pintype "bidirectional"))
      (node (ref "J4") (pin "1") (pinfunction "1_1") (pintype "passive"))
      (node (ref "PROG") (pin "4") (pinfunction "P$4_4") (pintype "bidirectional"))
      (node (ref "R1") (pin "1") (pinfunction "1_1") (pintype "passive"))
      (node (ref "U1") (pin "38") (pinfunction "~{RST}_38") (pintype "input"))
    )
    (net (code "106") (name "~{RS_RX}") (class "Default")
      (node (ref "RS485") (pin "2") (pinfunction "2_2") (pintype "bidirectional"))
      (node (ref "SN75") (pin "7") (pinfunction "B_7") (pintype "output"))
    )
    (net (code "107") (name "~{RS_TX}") (class "Default")
      (node (ref "R29") (pin "1") (pinfunction "1_1") (pintype "passive"))
      (node (ref "R3") (pin "1") (pinfunction "1_1") (pintype "passive"))
      (node (ref "RS485") (pin "4") (pinfunction "4_4") (pintype "bidirectional"))
      (node (ref "SN75") (pin "6") (pinfunction "Z_6") (pintype "output"))
    )
  )
)
